# c_meter.net
KiCad netlist of a schematic drawn in Altium Designer
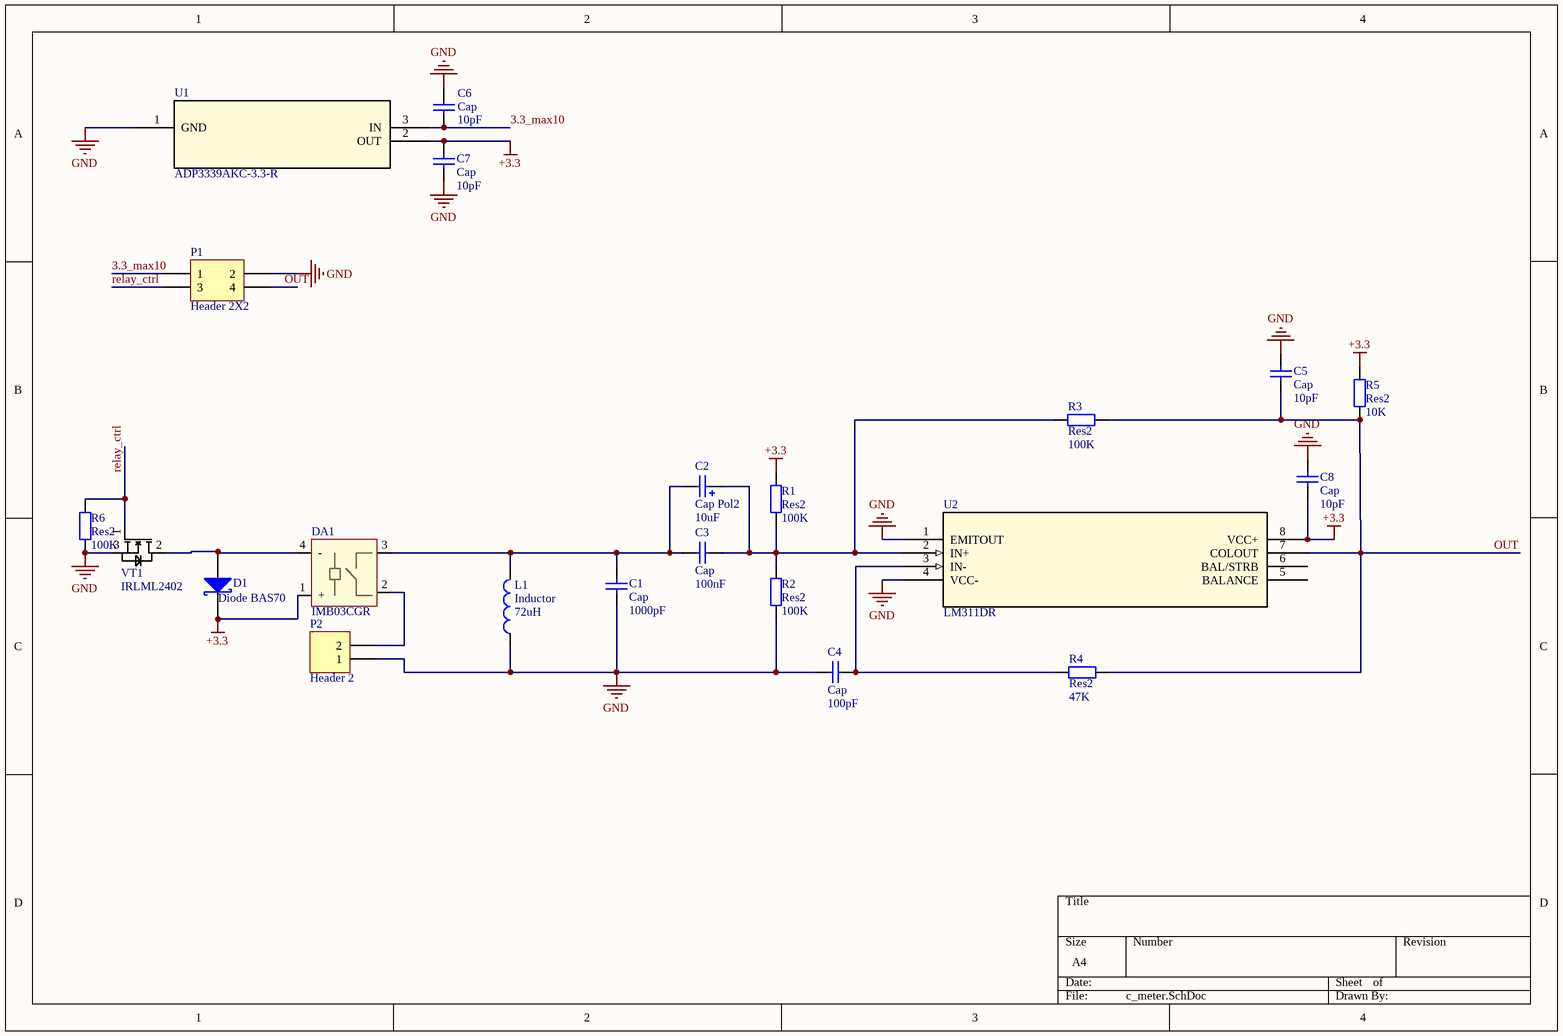
[diagram p0: c_meter.SchDoc]

(export (version "E")
  (design (tool "Eeschema 10.0.6"))
  (components
    (comp (ref "C1")
      (value "Cap")
      (footprint "Miscellaneous Devices:C0805")
      (description "Capacitor")
      (fields (field (name "ALTIUM_VALUE") "1000pF") (field (name "PUBLISHER") "Altium Limited"))
      (libsource (lib "Miscellaneous Devices") (part "Cap"))
    )
    (comp (ref "C2")
      (value "Cap Pol2")
      (footprint "Miscellaneous Devices:CAPR5-4X5")
      (description "Polarized Capacitor (Axial)")
      (fields (field (name "ALTIUM_VALUE") "10uF") (field (name "PUBLISHER") "Altium Limited"))
      (libsource (lib "Miscellaneous Devices") (part "Cap Pol2"))
    )
    (comp (ref "C3")
      (value "Cap")
      (footprint "Miscellaneous Devices:C0805")
      (description "Capacitor")
      (fields (field (name "ALTIUM_VALUE") "100nF") (field (name "PUBLISHER") "Altium Limited"))
      (libsource (lib "Miscellaneous Devices") (part "Cap"))
    )
    (comp (ref "C4")
      (value "Cap")
      (footprint "Miscellaneous Devices:C0805")
      (description "Capacitor")
      (fields (field (name "ALTIUM_VALUE") "100pF") (field (name "PUBLISHER") "Altium Limited"))
      (libsource (lib "Miscellaneous Devices") (part "Cap"))
    )
    (comp (ref "C5")
      (value "Cap")
      (footprint "Miscellaneous Devices:C0805")
      (description "Capacitor")
      (fields (field (name "ALTIUM_VALUE") "10pF") (field (name "PUBLISHER") "Altium Limited"))
      (libsource (lib "Miscellaneous Devices") (part "Cap"))
    )
    (comp (ref "C6")
      (value "Cap")
      (footprint "Miscellaneous Devices:C0805")
      (description "Capacitor")
      (fields (field (name "ALTIUM_VALUE") "10pF") (field (name "PUBLISHER") "Altium Limited"))
      (libsource (lib "Miscellaneous Devices") (part "Cap"))
    )
    (comp (ref "C7")
      (value "Cap")
      (footprint "Miscellaneous Devices:C0805")
      (description "Capacitor")
      (fields (field (name "ALTIUM_VALUE") "10pF") (field (name "PUBLISHER") "Altium Limited"))
      (libsource (lib "Miscellaneous Devices") (part "Cap"))
    )
    (comp (ref "C8")
      (value "Cap")
      (footprint "Miscellaneous Devices:C0805")
      (description "Capacitor")
      (fields (field (name "ALTIUM_VALUE") "10pF") (field (name "PUBLISHER") "Altium Limited"))
      (libsource (lib "Miscellaneous Devices") (part "Cap"))
    )
    (comp (ref "D1")
      (value "Diode BAS70")
      (footprint "SOT-23_N")
      (description "Silicon AF Schottky Diode for High-Speed Switching")
      (fields (field (name "PUBLISHER") "Altium Limited"))
      (libsource (lib "Miscellaneous Devices") (part "Diode BAS70"))
    )
    (comp (ref "DA1")
      (value "IMB03CGR")
      (footprint "IMB03CGR:IMB03CGR")
      (description "Relay")
      (libsource (lib "IMB03CGR") (part "IMB03CGR"))
    )
    (comp (ref "L1")
      (value "Inductor")
      (footprint "Miscellaneous Devices:AXIAL-0.5")
      (fields (field (name "ALTIUM_VALUE") "72uH") (field (name "PUBLISHER") "Altium Limited"))
      (libsource (lib "Miscellaneous Devices") (part "Inductor"))
    )
    (comp (ref "P1")
      (value "Header 2X2")
      (footprint "HDR2X2")
      (description "Header, 2-Pin, Dual row")
      (fields (field (name "PUBLISHER") "Altium Limited"))
      (libsource (lib "Miscellaneous Connectors") (part "Header 2X2"))
    )
    (comp (ref "P2")
      (value "Header 2")
      (footprint "HDR1X2")
      (description "Header, 2-Pin")
      (fields (field (name "PUBLISHER") "Altium Limited"))
      (libsource (lib "Miscellaneous Connectors") (part "Header 2"))
    )
    (comp (ref "R1")
      (value "Res2")
      (footprint "Miscellaneous Devices:6-0805_N")
      (description "Resistor")
      (fields (field (name "ALTIUM_VALUE") "100K") (field (name "PUBLISHER") "Altium Limited"))
      (libsource (lib "") (part "Res2_1"))
    )
    (comp (ref "R2")
      (value "Res2")
      (footprint "Miscellaneous Devices:6-0805_N")
      (description "Resistor")
      (fields (field (name "ALTIUM_VALUE") "100K") (field (name "PUBLISHER") "Altium Limited"))
      (libsource (lib "") (part "Res2_1"))
    )
    (comp (ref "R3")
      (value "Res2")
      (footprint "Miscellaneous Devices:6-0805_N")
      (description "Resistor")
      (fields (field (name "ALTIUM_VALUE") "100K") (field (name "PUBLISHER") "Altium Limited"))
      (libsource (lib "Miscellaneous Devices") (part "Res2"))
    )
    (comp (ref "R4")
      (value "Res2")
      (footprint "Miscellaneous Devices:6-0805_N")
      (description "Resistor")
      (fields (field (name "ALTIUM_VALUE") "47K") (field (name "PUBLISHER") "Altium Limited"))
      (libsource (lib "Miscellaneous Devices") (part "Res2"))
    )
    (comp (ref "R5")
      (value "Res2")
      (footprint "Miscellaneous Devices:6-0805_N")
      (description "Resistor")
      (fields (field (name "ALTIUM_VALUE") "10K") (field (name "PUBLISHER") "Altium Limited"))
      (libsource (lib "") (part "Res2_1"))
    )
    (comp (ref "R6")
      (value "Res2")
      (footprint "Miscellaneous Devices:6-0805_N")
      (description "Resistor")
      (fields (field (name "ALTIUM_VALUE") "100K") (field (name "PUBLISHER") "Altium Limited"))
      (libsource (lib "") (part "Res2_1"))
    )
    (comp (ref "U1")
      (value "ADP3339AKC-3.3-R")
      (footprint "KC_3")
      (description "Imported")
      (fields (field (name "MANUFACTURER_PART_NUMBER") "ADP3339AKC-3.3-RL"))
      (libsource (lib "adp3339akc-3") (part "ADP3339AKC-3.3-R"))
    )
    (comp (ref "U2")
      (value "LM311DR")
      (footprint "D8")
      (description "Imported")
      (fields (field (name "MANUFACTURER") "Texas Instruments"))
      (libsource (lib "lm311dr") (part "LM311DR"))
    )
    (comp (ref "VT1")
      (value "IRLML2402")
      (footprint "IMB03CGR:IRLML2402")
      (description "Voltage Source")
      (fields (field (name "PUBLISHER") "Altium Limited"))
      (libsource (lib "IMB03CGR") (part "IRLML2402"))
    )
  )
  (nets
    (net (code "1") (name "+3.3") (class "Default")
      (node (ref "C7") (pin "1") (pinfunction "1_1") (pintype "passive"))
      (node (ref "C8") (pin "2") (pinfunction "2_2") (pintype "passive"))
      (node (ref "D1") (pin "3") (pinfunction "K_3") (pintype "passive"))
      (node (ref "DA1") (pin "1") (pinfunction "+_1") (pintype "power_in"))
      (node (ref "R1") (pin "2") (pinfunction "2_2") (pintype "passive"))
      (node (ref "R5") (pin "2") (pinfunction "2_2") (pintype "passive"))
      (node (ref "U1") (pin "2") (pinfunction "OUT_2") (pintype "passive"))
      (node (ref "U2") (pin "8") (pinfunction "VCC+_8") (pintype "power_in"))
    )
    (net (code "2") (name "/3.3_max10") (class "Default")
      (node (ref "C6") (pin "2") (pinfunction "2_2") (pintype "passive"))
      (node (ref "P1") (pin "1") (pinfunction "1_1") (pintype "passive"))
      (node (ref "U1") (pin "3") (pinfunction "IN_3") (pintype "passive"))
    )
    (net (code "3") (name "/OUT") (class "Default")
      (node (ref "C5") (pin "1") (pinfunction "1_1") (pintype "passive"))
      (node (ref "P1") (pin "4") (pinfunction "4_4") (pintype "passive"))
      (node (ref "R3") (pin "2") (pinfunction "2_2") (pintype "passive"))
      (node (ref "R4") (pin "2") (pinfunction "2_2") (pintype "passive"))
      (node (ref "R5") (pin "1") (pinfunction "1_1") (pintype "passive"))
      (node (ref "U2") (pin "7") (pinfunction "COLOUT_7") (pintype "open_collector"))
    )
    (net (code "4") (name "/relay_ctrl") (class "Default")
      (node (ref "P1") (pin "3") (pinfunction "3_3") (pintype "passive"))
      (node (ref "R6") (pin "2") (pinfunction "2_2") (pintype "passive"))
      (node (ref "VT1") (pin "1") (pinfunction "G_1") (pintype "passive"))
    )
    (net (code "5") (name "GND") (class "Default")
      (node (ref "C1") (pin "1") (pinfunction "1_1") (pintype "passive"))
      (node (ref "C4") (pin "1") (pinfunction "1_1") (pintype "passive"))
      (node (ref "C5") (pin "2") (pinfunction "2_2") (pintype "passive"))
      (node (ref "C6") (pin "1") (pinfunction "1_1") (pintype "passive"))
      (node (ref "C7") (pin "2") (pinfunction "2_2") (pintype "passive"))
      (node (ref "C8") (pin "1") (pinfunction "1_1") (pintype "passive"))
      (node (ref "L1") (pin "1") (pinfunction "1_1") (pintype "passive"))
      (node (ref "P1") (pin "2") (pinfunction "2_2") (pintype "passive"))
      (node (ref "P2") (pin "1") (pinfunction "1_1") (pintype "passive"))
      (node (ref "R2") (pin "1") (pinfunction "1_1") (pintype "passive"))
      (node (ref "R6") (pin "1") (pinfunction "1_1") (pintype "passive"))
      (node (ref "U1") (pin "1") (pinfunction "GND_1") (pintype "passive"))
      (node (ref "U2") (pin "1") (pinfunction "EMITOUT_1") (pintype "open_emitter"))
      (node (ref "U2") (pin "4") (pinfunction "VCC-_4") (pintype "power_in"))
      (node (ref "VT1") (pin "3") (pinfunction "D_3") (pintype "power_in"))
    )
    (net (code "6") (name "Net-(C1-Pad2)") (class "Default")
      (node (ref "C1") (pin "2") (pinfunction "2_2") (pintype "passive"))
      (node (ref "C2") (pin "2") (pinfunction "2_2") (pintype "passive"))
      (node (ref "C3") (pin "1") (pinfunction "1_1") (pintype "passive"))
      (node (ref "DA1") (pin "3") (pintype "passive"))
      (node (ref "L1") (pin "2") (pinfunction "2_2") (pintype "passive"))
    )
    (net (code "7") (name "Net-(D1-A)") (class "Default")
      (node (ref "D1") (pin "1") (pinfunction "A_1") (pintype "passive"))
      (node (ref "DA1") (pin "4") (pinfunction "-_4") (pintype "power_in"))
      (node (ref "VT1") (pin "2") (pinfunction "S_2") (pintype "passive"))
    )
    (net (code "8") (name "Net-(DA1-Pad2)") (class "Default")
      (node (ref "DA1") (pin "2") (pintype "passive"))
      (node (ref "P2") (pin "2") (pinfunction "2_2") (pintype "passive"))
    )
    (net (code "9") (name "Net-(U2-IN+)") (class "Default")
      (node (ref "C2") (pin "1") (pinfunction "1_1") (pintype "passive"))
      (node (ref "C3") (pin "2") (pinfunction "2_2") (pintype "passive"))
      (node (ref "R1") (pin "1") (pinfunction "1_1") (pintype "passive"))
      (node (ref "R2") (pin "2") (pinfunction "2_2") (pintype "passive"))
      (node (ref "R3") (pin "1") (pinfunction "1_1") (pintype "passive"))
      (node (ref "U2") (pin "2") (pinfunction "IN+_2") (pintype "input"))
    )
    (net (code "10") (name "Net-(U2-IN-)") (class "Default")
      (node (ref "C4") (pin "2") (pinfunction "2_2") (pintype "passive"))
      (node (ref "R4") (pin "1") (pinfunction "1_1") (pintype "passive"))
      (node (ref "U2") (pin "3") (pinfunction "IN-_3") (pintype "input"))
    )
    (net (code "11") (name "unconnected-(U2-BALANCE-Pad5)") (class "Default")
      (node (ref "U2") (pin "5") (pinfunction "BALANCE_5") (pintype "passive"))
    )
    (net (code "12") (name "unconnected-(U2-BAL{slash}STRB-Pad6)") (class "Default")
      (node (ref "U2") (pin "6") (pinfunction "BAL/STRB_6") (pintype "passive"))
    )
  )
)
